# 01_Power.net
KiCad netlist of a schematic drawn in Altium Designer
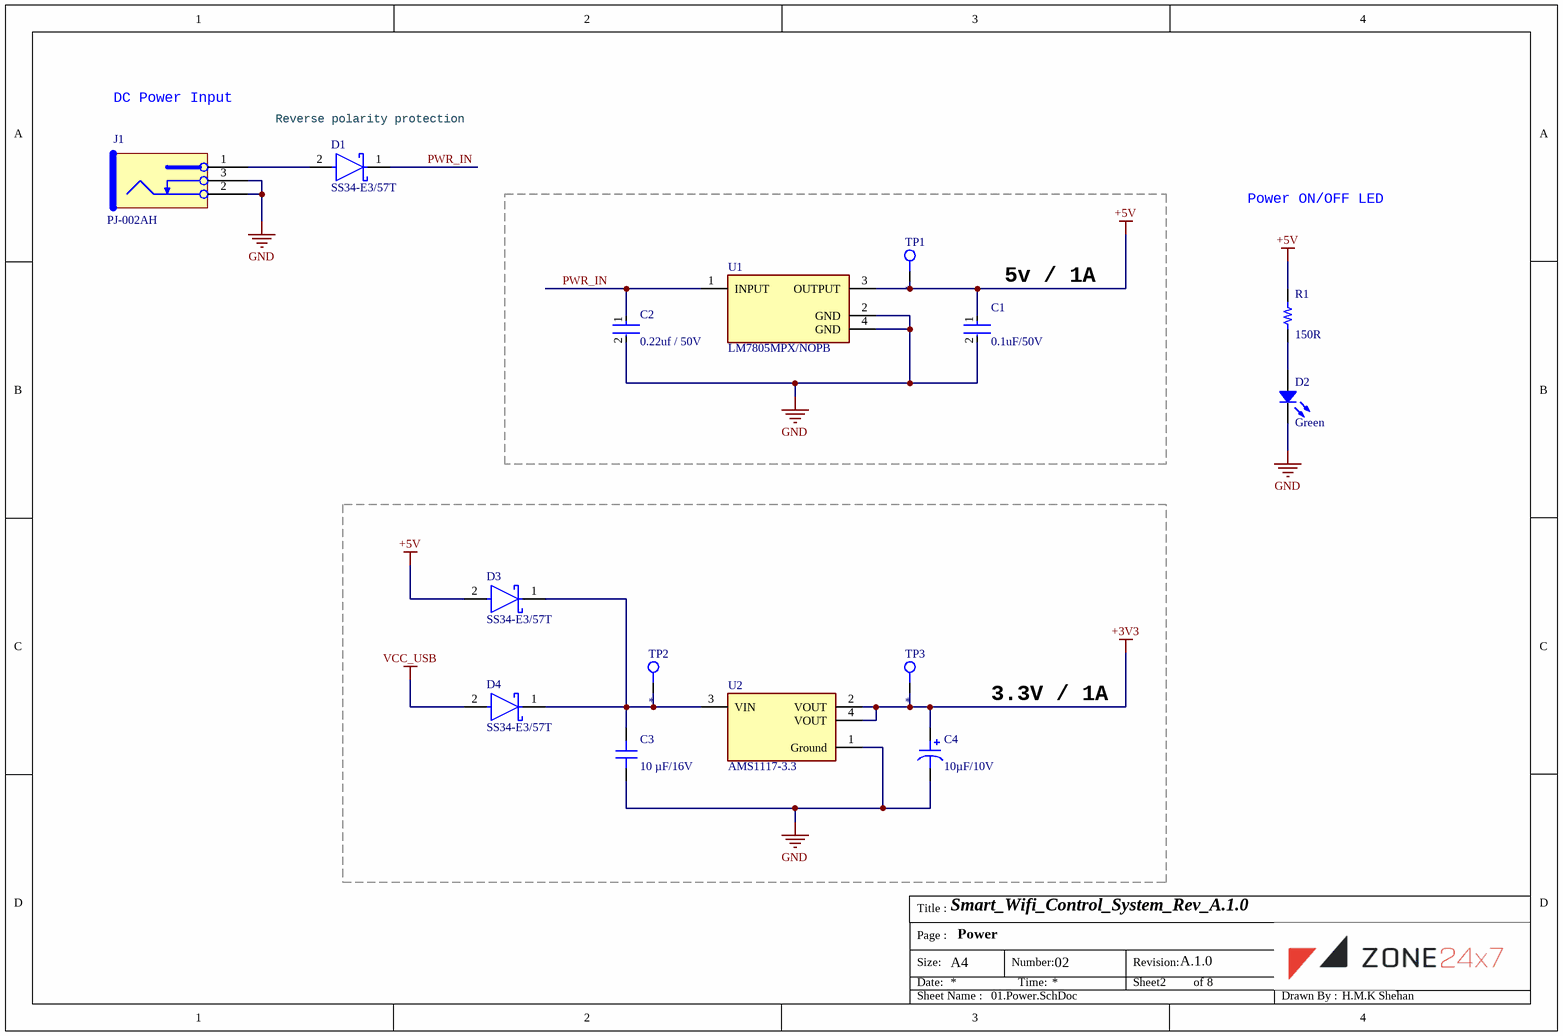
[diagram p0: 01.Power.SchDoc]

(export (version "E")
  (design (tool "Eeschema 10.0.6"))
  (components
    (comp (ref "C1")
      (value "0.1uF/50V")
      (footprint "FP-RDE0M1-MFG")
      (description "±10% 100nF 4mm 5.5mm 5mm 50V Radial Leaded,P=5mm Ceramic Disc Capacitors ROHS")
      (fields
        (field (name "MANUFACTURER PART NUMBER") "RDER71H104K0M1H03A")
        (field (name "JLC PART NUMBER") "C527620")
      )
      (libsource (lib "Altium Content Vault") (part "b4654b650e69147ec39a6b967a45e02"))
    )
    (comp (ref "C2")
      (value "0.22uf / 50V")
      (footprint "FP-GRM31C-0_2-e0_3_0_8-IPC_B")
      (description "50V 220nF C0G ±5% 1206 Multilayer Ceramic Capacitors MLCC - SMD/SMT ROHS")
      (fields (field (name "PART NUMBER") "GRM31C5C1H224JE02L") (field (name "JLC PART NUMBER") "C464977"))
      (libsource (lib "Altium Content Vault") (part "02cd4be3c70576c341d710602a673aa"))
    )
    (comp (ref "C3")
      (value "10 µF/16V")
      (footprint "CAP 0603_1608")
      (description "16V 10uF X5R ±20% 0603 Multilayer Ceramic Capacitors MLCC - SMD/SMT ROHS")
      (fields
        (field (name "MANUFACTURER PART NUMBER") "GRT188R61C106ME13D")
        (field (name "MANUFACTURER") "Murata Electronics")
      )
      (libsource (lib "Celestial Altium Library - altium_library") (part "Capacitor"))
    )
    (comp (ref "C4")
      (value "10µF/10V")
      (footprint "CAP POL 1411_3528")
      (description "10uF 10V 2.1Ω@100kHz ±10% 1411 Tantalum Capacitors ROHS")
      (fields
        (field (name "MANUFACTURER PART NUMBER") "TAJB106K010TNJ")
        (field (name "MANUFACTURER") "AVX Corporation")
      )
      (libsource (lib "Celestial Altium Library - altium_library") (part "Polarised Capacitor"))
    )
    (comp (ref "D1")
      (value "SS34-E3/57T")
      (footprint "FP-95402-MFG")
      (description "40V 500mV@3A 3A SMC(DO-214AB) Schottky Barrier Diodes (SBD) ROHS")
      (fields (field (name "JLC PART NUMBER") "C13354"))
      (libsource (lib "Altium Content Vault") (part "1d6ec82d83fb6aee721767c19dac4b9"))
    )
    (comp (ref "D2")
      (value "Green")
      (footprint "LED 0805_2012 GREEN")
      (description "无色透明透镜 570nm -40℃~+90℃ Green-yellow 120° 0805 Light Emitting Diodes (LED) ROHS")
      (fields
        (field (name "MANUFACTURER PART NUMBER") "E6C0805YGAC1UDA")
        (field (name "MANUFACTURER") "EKINGLUX")
      )
      (libsource (lib "Celestial Altium Library - altium_library") (part "LED"))
    )
    (comp (ref "D3")
      (value "SS34-E3/57T")
      (footprint "FP-95402-MFG")
      (description "40V 500mV@3A 3A SMC(DO-214AB) Schottky Barrier Diodes (SBD) ROHS")
      (fields (field (name "JLC PART NUMBER") "C13354"))
      (libsource (lib "Altium Content Vault") (part "1d6ec82d83fb6aee721767c19dac4b9"))
    )
    (comp (ref "D4")
      (value "SS34-E3/57T")
      (footprint "FP-95402-MFG")
      (description "40V 500mV@3A 3A SMC(DO-214AB) Schottky Barrier Diodes (SBD) ROHS")
      (fields (field (name "JLC PART NUMBER") "C13354"))
      (libsource (lib "Altium Content Vault") (part "1d6ec82d83fb6aee721767c19dac4b9"))
    )
    (comp (ref "J1")
      (value "PJ-002AH")
      (footprint "POWER_JACK_5.5_2.1MM_NS")
      (description "CONN PWR JACK 2.1X5.5MM HIGH CUR")
      (fields (field (name "JLC PART NUMBER") "C2961147"))
      (libsource (lib "Smart_Wifi_Control_System_Rev_A.1.0") (part "PJ-002AH"))
    )
    (comp (ref "R1")
      (value "150R")
      (footprint "RES 0603_1608")
      (fields
        (field (name "MANUFACTURER PART NUMBER") "CRCW0603150RFKEA")
        (field (name "MANUFACTURER") "Vishay Dale")
        (field (name "JLC PART NUMBER") "C844741")
      )
      (libsource (lib "Celestial Altium Library - altium_library") (part "Resistor"))
    )
    (comp (ref "TP1")
      (value "*")
      (footprint "TP-2ED-1ID")
      (description "Test point-via type 2mm External diameter  1mm internal diameter")
      (libsource (lib "Smart_Wifi_Control_System_Rev_A.1.0") (part "TP-2ED-1ID"))
    )
    (comp (ref "TP2")
      (value "*")
      (footprint "TP-2ED-1ID")
      (description "Test point-via type 2mm External diameter  1mm internal diameter")
      (libsource (lib "Smart_Wifi_Control_System_Rev_A.1.0") (part "TP-2ED-1ID"))
    )
    (comp (ref "TP3")
      (value "*")
      (footprint "TP-2ED-1ID")
      (description "Test point-via type 2mm External diameter  1mm internal diameter")
      (libsource (lib "Smart_Wifi_Control_System_Rev_A.1.0") (part "TP-2ED-1ID"))
    )
    (comp (ref "U1")
      (value "LM7805MPX/NOPB")
      (footprint "FP-LM7805MPX-NOPB-MFG")
      (description "80dB@(120Hz) 1.5A null 5V positive 35V SOT-223-4 Linear Voltage Regulators (LDO) ROHS")
      (fields (field (name "JLC PART NUMBER") "C2848241"))
      (libsource (lib "Altium Content Vault") (part "b4ee7691a89d8e73302b24c49f391f2"))
    )
    (comp (ref "U2")
      (value "AMS1117-3.3")
      (footprint "FP-AMS1117-IPC_C")
      (description "SOT-223 Linear Voltage Regulators (LDO) ROHS")
      (fields
        (field (name "MANUFACTURER") "Advanced Monolithic Systems")
        (field (name "JLC PART NUMBER") "C6186")
      )
      (libsource (lib "Altium Content Vault") (part "8bdbb5f8e77002000e30dd2845d0354"))
    )
  )
  (nets
    (net (code "1") (name "+3V3") (class "Default")
      (node (ref "C4") (pin "1") (pinfunction "1_1") (pintype "passive"))
      (node (ref "TP3") (pin "1") (pinfunction "1_1") (pintype "passive"))
      (node (ref "U2") (pin "2") (pinfunction "VOUT_2") (pintype "passive"))
      (node (ref "U2") (pin "4") (pinfunction "VOUT_4") (pintype "passive"))
    )
    (net (code "2") (name "+5V") (class "Default")
      (node (ref "C1") (pin "1") (pinfunction "1_1") (pintype "passive"))
      (node (ref "D3") (pin "2") (pinfunction "A_2") (pintype "passive"))
      (node (ref "R1") (pin "2") (pinfunction "2_2") (pintype "passive"))
      (node (ref "TP1") (pin "1") (pinfunction "1_1") (pintype "passive"))
      (node (ref "U1") (pin "3") (pinfunction "OUTPUT_3") (pintype "passive"))
    )
    (net (code "3") (name "/PWR_IN") (class "Default")
      (node (ref "C2") (pin "1") (pinfunction "1_1") (pintype "passive"))
      (node (ref "D1") (pin "1") (pinfunction "C_1") (pintype "passive"))
      (node (ref "U1") (pin "1") (pinfunction "INPUT_1") (pintype "power_in"))
    )
    (net (code "4") (name "GND") (class "Default")
      (node (ref "C1") (pin "2") (pinfunction "2_2") (pintype "passive"))
      (node (ref "C2") (pin "2") (pinfunction "2_2") (pintype "passive"))
      (node (ref "C3") (pin "1") (pinfunction "1_1") (pintype "passive"))
      (node (ref "C4") (pin "2") (pinfunction "2_2") (pintype "passive"))
      (node (ref "D2") (pin "2") (pinfunction "2_2") (pintype "passive"))
      (node (ref "J1") (pin "2") (pinfunction "2_2") (pintype "passive"))
      (node (ref "J1") (pin "3") (pinfunction "3_3") (pintype "passive"))
      (node (ref "U1") (pin "2") (pinfunction "GND_2") (pintype "power_in"))
      (node (ref "U1") (pin "4") (pinfunction "GND_4") (pintype "power_in"))
      (node (ref "U2") (pin "1") (pinfunction "Ground_1") (pintype "power_in"))
    )
    (net (code "5") (name "Net-(D1-A)") (class "Default")
      (node (ref "D1") (pin "2") (pinfunction "A_2") (pintype "passive"))
      (node (ref "J1") (pin "1") (pinfunction "1_1") (pintype "passive"))
    )
    (net (code "6") (name "Net-(D2-Pad1)") (class "Default")
      (node (ref "D2") (pin "1") (pinfunction "1_1") (pintype "passive"))
      (node (ref "R1") (pin "1") (pinfunction "1_1") (pintype "passive"))
    )
    (net (code "7") (name "Net-(D3-C)") (class "Default")
      (node (ref "C3") (pin "2") (pinfunction "2_2") (pintype "passive"))
      (node (ref "D3") (pin "1") (pinfunction "C_1") (pintype "passive"))
      (node (ref "D4") (pin "1") (pinfunction "C_1") (pintype "passive"))
      (node (ref "TP2") (pin "1") (pinfunction "1_1") (pintype "passive"))
      (node (ref "U2") (pin "3") (pinfunction "VIN_3") (pintype "power_in"))
    )
    (net (code "8") (name "VCC_USB") (class "Default")
      (node (ref "D4") (pin "2") (pinfunction "A_2") (pintype "passive"))
    )
  )
)
